# MCU.net
KiCad netlist of a schematic drawn in Altium Designer
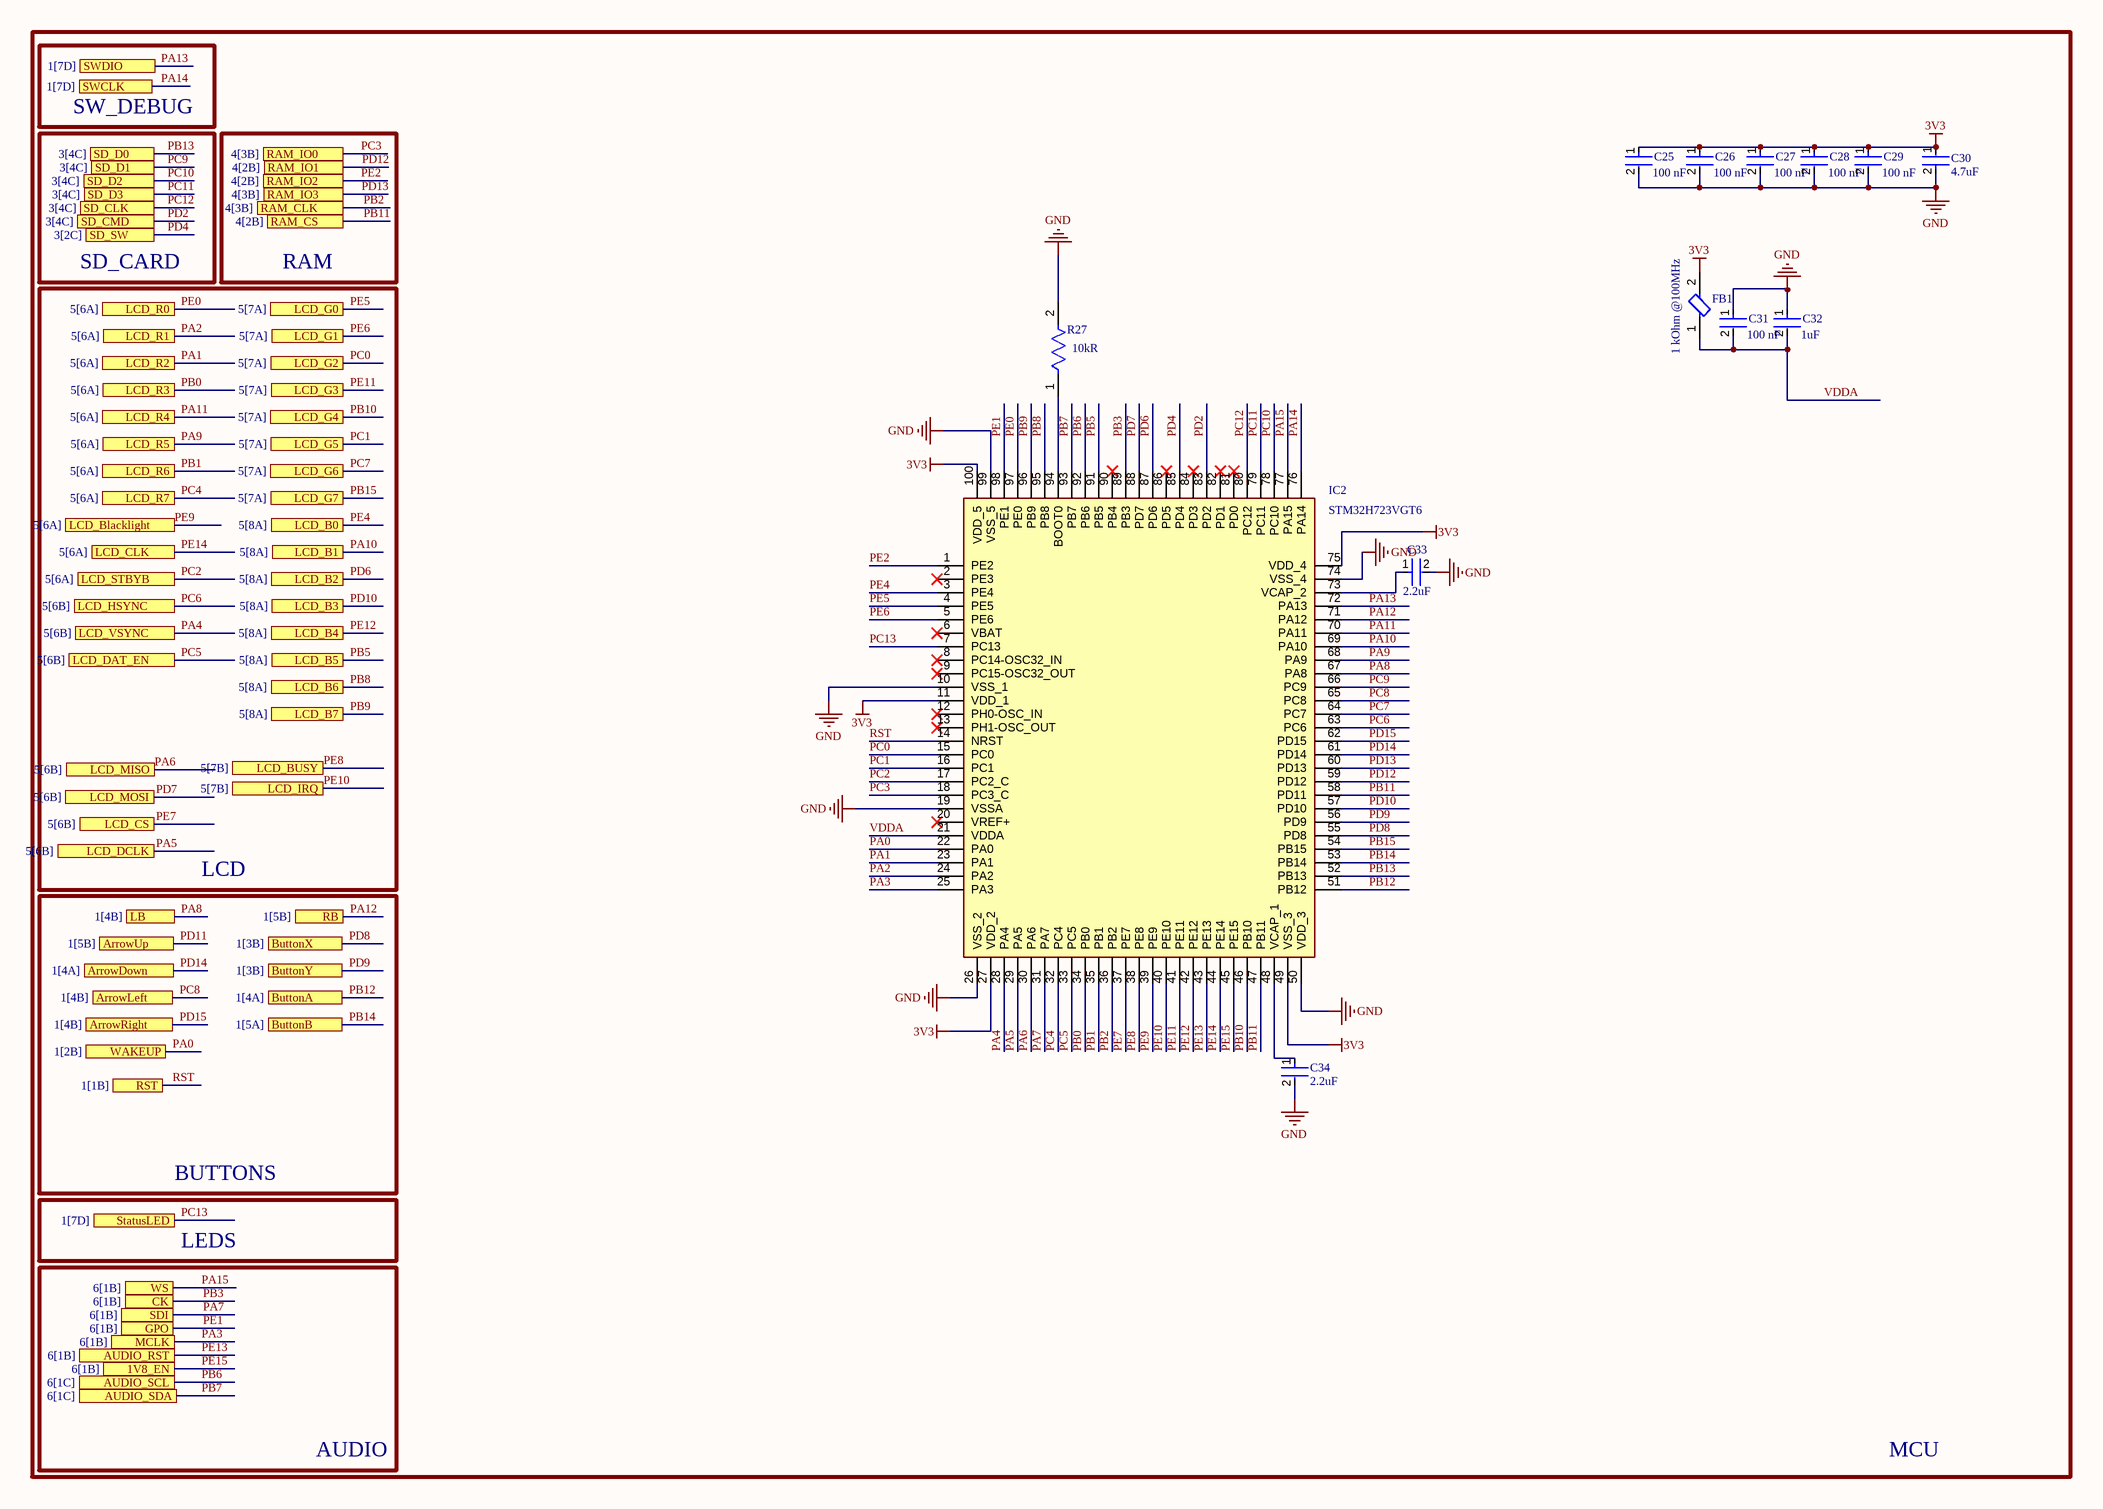
[diagram p0: MCU.SchDoc]

(export (version "E")
  (design (tool "Eeschema 10.0.6"))
  (components
    (comp (ref "C25")
      (value "100 nF")
      (footprint "FP-AC0402-0_5-MFG")
      (description "0.10µF 16V Ceramic Capacitor X7R 0402 (1005 Metric) 0.039\" L x 0.020\" W (1.00mm x 0.50mm)")
      (fields (field (name "MANUFACTURER") "Yageo") (field (name "TOLERANCE") "0.1"))
      (libsource (lib "Altium Content Vault") (part "11868f565c42a9108669ba33697ecf6"))
    )
    (comp (ref "C26")
      (value "100 nF")
      (footprint "FP-AC0402-0_5-MFG")
      (description "0.10µF 16V Ceramic Capacitor X7R 0402 (1005 Metric) 0.039\" L x 0.020\" W (1.00mm x 0.50mm)")
      (fields (field (name "MANUFACTURER") "Yageo") (field (name "TOLERANCE") "0.1"))
      (libsource (lib "Altium Content Vault") (part "11868f565c42a9108669ba33697ecf6"))
    )
    (comp (ref "C27")
      (value "100 nF")
      (footprint "FP-AC0402-0_5-MFG")
      (description "0.10µF 16V Ceramic Capacitor X7R 0402 (1005 Metric) 0.039\" L x 0.020\" W (1.00mm x 0.50mm)")
      (fields (field (name "MANUFACTURER") "Yageo") (field (name "TOLERANCE") "0.1"))
      (libsource (lib "Altium Content Vault") (part "11868f565c42a9108669ba33697ecf6"))
    )
    (comp (ref "C28")
      (value "100 nF")
      (footprint "FP-AC0402-0_5-MFG")
      (description "0.10µF 16V Ceramic Capacitor X7R 0402 (1005 Metric) 0.039\" L x 0.020\" W (1.00mm x 0.50mm)")
      (fields (field (name "MANUFACTURER") "Yageo") (field (name "TOLERANCE") "0.1"))
      (libsource (lib "Altium Content Vault") (part "11868f565c42a9108669ba33697ecf6"))
    )
    (comp (ref "C29")
      (value "100 nF")
      (footprint "FP-AC0402-0_5-MFG")
      (description "0.10µF 16V Ceramic Capacitor X7R 0402 (1005 Metric) 0.039\" L x 0.020\" W (1.00mm x 0.50mm)")
      (fields (field (name "MANUFACTURER") "Yageo") (field (name "TOLERANCE") "0.1"))
      (libsource (lib "Altium Content Vault") (part "11868f565c42a9108669ba33697ecf6"))
    )
    (comp (ref "C30")
      (value "JMK105BBJ475MVHF")
      (footprint "FP-0402-L_1_0_0_15-W_0_5-IPC_B")
      (description "None")
      (fields (field (name "CAPACITANCE") "4.7uF") (field (name "TOLERANCE") "20%"))
      (libsource (lib "Altium Content Vault") (part "236180d848d6139a670b325ea6854c9"))
    )
    (comp (ref "C31")
      (value "100 nF")
      (footprint "FP-AC0402-0_5-MFG")
      (description "0.10µF 16V Ceramic Capacitor X7R 0402 (1005 Metric) 0.039\" L x 0.020\" W (1.00mm x 0.50mm)")
      (fields (field (name "MANUFACTURER") "Yageo") (field (name "TOLERANCE") "0.1"))
      (libsource (lib "Altium Content Vault") (part "11868f565c42a9108669ba33697ecf6"))
    )
    (comp (ref "C32")
      (value "GRM155C70J105KE11D")
      (footprint "FP-GRM155-0_1-IPC_A")
      (description "Chip Multilayer Ceramic Capacitors for General Purpose, 0402, 1.0uF, X7S, 22%, 10%, 6.3V")
      (fields (field (name "CAPACITANCE") "1uF") (field (name "TOLERANCE") "10%"))
      (libsource (lib "Altium Content Vault") (part "11868f565c42a9108669ba33697ecf6"))
    )
    (comp (ref "C33")
      (value "GRM155R61C225KE11D")
      (footprint "FP-GRM155-0_2-IPC_B")
      (description "Chip Multilayer Ceramic Capacitors for General Purpose, 0402, 2.2uF, X5R, 15%, 10%, 16V")
      (fields (field (name "TOLERANCE") "10%") (field (name "CAPACITANCE") "2.2uF"))
      (libsource (lib "Altium Content Vault") (part "b4654b650e69147ec39a6b967a45e02"))
    )
    (comp (ref "C34")
      (value "GRM155R61C225KE11D")
      (footprint "FP-GRM155-0_2-IPC_B")
      (description "Chip Multilayer Ceramic Capacitors for General Purpose, 0402, 2.2uF, X5R, 15%, 10%, 16V")
      (fields (field (name "TOLERANCE") "10%") (field (name "CAPACITANCE") "2.2uF"))
      (libsource (lib "Altium Content Vault") (part "b4654b650e69147ec39a6b967a45e02"))
    )
    (comp (ref "FB1")
      (value "1 kOhm @100MHz")
      (footprint "FP-BLM21-0_2-t0_85-e0_5-d-IPC_A")
      (description "Chip Ferrite Bead, 0805, 1000Ω @ 100MHz, 0.12Ω, 25%, 1.6A")
      (fields (field (name "Comment") "BLM21SP102SN1D"))
      (libsource (lib "Altium Content Vault") (part "5f30dd21d616792df468990f7003faa"))
    )
    (comp (ref "IC2")
      (value "STM32H723VGT6")
      (footprint "SamacSys:QFP50P1600X1600X160-100N")
      (description "Integrated Circuit")
      (fields (field (name "MOUSER PART NUMBER") "511-STM32H723VGT6"))
      (libsource (lib "*") (part "STM32H723VGT6"))
    )
    (comp (ref "R27")
      (value "RK73H1ETTPD1002F")
      (footprint "FP-RK73H1E-IPC_C")
      (description "10kΩ ±1% 0.1W Chip Resistor 0402 Thick Film AEC-Q200 Qualified")
      (fields (field (name "RESISTANCE") "10kR"))
      (libsource (lib "Altium Content Vault") (part "1029c3af85768c4190bb7ad29bc67b5"))
    )
  )
  (nets
    (net (code "3") (name "/PA0") (class "Default")
      (node (ref "IC2") (pin "22") (pinfunction "PA0_22") (pintype "passive"))
    )
    (net (code "4") (name "/PA1") (class "Default")
      (node (ref "IC2") (pin "23") (pinfunction "PA1_23") (pintype "passive"))
    )
    (net (code "5") (name "/PA2") (class "Default")
      (node (ref "IC2") (pin "24") (pinfunction "PA2_24") (pintype "passive"))
    )
    (net (code "6") (name "/PA3") (class "Default")
      (node (ref "IC2") (pin "25") (pinfunction "PA3_25") (pintype "passive"))
    )
    (net (code "7") (name "/PA4") (class "Default")
      (node (ref "IC2") (pin "28") (pinfunction "PA4_28") (pintype "passive"))
    )
    (net (code "8") (name "/PA5") (class "Default")
      (node (ref "IC2") (pin "29") (pinfunction "PA5_29") (pintype "passive"))
    )
    (net (code "9") (name "/PA6") (class "Default")
      (node (ref "IC2") (pin "30") (pinfunction "PA6_30") (pintype "passive"))
    )
    (net (code "10") (name "/PA7") (class "Default")
      (node (ref "IC2") (pin "31") (pinfunction "PA7_31") (pintype "passive"))
    )
    (net (code "11") (name "/PA8") (class "Default")
      (node (ref "IC2") (pin "67") (pinfunction "PA8_67") (pintype "passive"))
    )
    (net (code "12") (name "/PA9") (class "Default")
      (node (ref "IC2") (pin "68") (pinfunction "PA9_68") (pintype "passive"))
    )
    (net (code "13") (name "/PA10") (class "Default")
      (node (ref "IC2") (pin "69") (pinfunction "PA10_69") (pintype "passive"))
    )
    (net (code "14") (name "/PA11") (class "Default")
      (node (ref "IC2") (pin "70") (pinfunction "PA11_70") (pintype "passive"))
    )
    (net (code "15") (name "/PA12") (class "Default")
      (node (ref "IC2") (pin "71") (pinfunction "PA12_71") (pintype "passive"))
    )
    (net (code "16") (name "/PA13") (class "Default")
      (node (ref "IC2") (pin "72") (pinfunction "PA13_72") (pintype "passive"))
    )
    (net (code "17") (name "/PA14") (class "Default")
      (node (ref "IC2") (pin "76") (pinfunction "PA14_76") (pintype "passive"))
    )
    (net (code "18") (name "/PA15") (class "Default")
      (node (ref "IC2") (pin "77") (pinfunction "PA15_77") (pintype "passive"))
    )
    (net (code "19") (name "/PB0") (class "Default")
      (node (ref "IC2") (pin "34") (pinfunction "PB0_34") (pintype "passive"))
    )
    (net (code "20") (name "/PB1") (class "Default")
      (node (ref "IC2") (pin "35") (pinfunction "PB1_35") (pintype "passive"))
    )
    (net (code "21") (name "/PB2") (class "Default")
      (node (ref "IC2") (pin "36") (pinfunction "PB2_36") (pintype "passive"))
    )
    (net (code "22") (name "/PB3") (class "Default")
      (node (ref "IC2") (pin "89") (pinfunction "PB3_89") (pintype "passive"))
    )
    (net (code "23") (name "/PB5") (class "Default")
      (node (ref "IC2") (pin "91") (pinfunction "PB5_91") (pintype "passive"))
    )
    (net (code "24") (name "/PB6") (class "Default")
      (node (ref "IC2") (pin "92") (pinfunction "PB6_92") (pintype "passive"))
    )
    (net (code "25") (name "/PB7") (class "Default")
      (node (ref "IC2") (pin "93") (pinfunction "PB7_93") (pintype "passive"))
    )
    (net (code "26") (name "/PB8") (class "Default")
      (node (ref "IC2") (pin "95") (pinfunction "PB8_95") (pintype "passive"))
    )
    (net (code "27") (name "/PB9") (class "Default")
      (node (ref "IC2") (pin "96") (pinfunction "PB9_96") (pintype "passive"))
    )
    (net (code "28") (name "/PB10") (class "Default")
      (node (ref "IC2") (pin "46") (pinfunction "PB10_46") (pintype "passive"))
    )
    (net (code "29") (name "/PB11") (class "Default")
      (node (ref "IC2") (pin "47") (pinfunction "PB11_47") (pintype "passive"))
      (node (ref "IC2") (pin "58") (pinfunction "PD11_58") (pintype "passive"))
    )
    (net (code "30") (name "/PB12") (class "Default")
      (node (ref "IC2") (pin "51") (pinfunction "PB12_51") (pintype "passive"))
    )
    (net (code "31") (name "/PB13") (class "Default")
      (node (ref "IC2") (pin "52") (pinfunction "PB13_52") (pintype "passive"))
    )
    (net (code "32") (name "/PB14") (class "Default")
      (node (ref "IC2") (pin "53") (pinfunction "PB14_53") (pintype "passive"))
    )
    (net (code "33") (name "/PB15") (class "Default")
      (node (ref "IC2") (pin "54") (pinfunction "PB15_54") (pintype "passive"))
    )
    (net (code "34") (name "/PC0") (class "Default")
      (node (ref "IC2") (pin "15") (pinfunction "PC0_15") (pintype "passive"))
    )
    (net (code "35") (name "/PC1") (class "Default")
      (node (ref "IC2") (pin "16") (pinfunction "PC1_16") (pintype "passive"))
    )
    (net (code "36") (name "/PC2") (class "Default")
      (node (ref "IC2") (pin "17") (pinfunction "PC2_C_17") (pintype "passive"))
    )
    (net (code "37") (name "/PC3") (class "Default")
      (node (ref "IC2") (pin "18") (pinfunction "PC3_C_18") (pintype "passive"))
    )
    (net (code "38") (name "/PC4") (class "Default")
      (node (ref "IC2") (pin "32") (pinfunction "PC4_32") (pintype "passive"))
    )
    (net (code "39") (name "/PC5") (class "Default")
      (node (ref "IC2") (pin "33") (pinfunction "PC5_33") (pintype "passive"))
    )
    (net (code "40") (name "/PC6") (class "Default")
      (node (ref "IC2") (pin "63") (pinfunction "PC6_63") (pintype "passive"))
    )
    (net (code "41") (name "/PC7") (class "Default")
      (node (ref "IC2") (pin "64") (pinfunction "PC7_64") (pintype "passive"))
    )
    (net (code "42") (name "/PC8") (class "Default")
      (node (ref "IC2") (pin "65") (pinfunction "PC8_65") (pintype "passive"))
    )
    (net (code "43") (name "/PC9") (class "Default")
      (node (ref "IC2") (pin "66") (pinfunction "PC9_66") (pintype "passive"))
    )
    (net (code "44") (name "/PC10") (class "Default")
      (node (ref "IC2") (pin "78") (pinfunction "PC10_78") (pintype "passive"))
    )
    (net (code "45") (name "/PC11") (class "Default")
      (node (ref "IC2") (pin "79") (pinfunction "PC11_79") (pintype "passive"))
    )
    (net (code "46") (name "/PC12") (class "Default")
      (node (ref "IC2") (pin "80") (pinfunction "PC12_80") (pintype "passive"))
    )
    (net (code "47") (name "/PC13") (class "Default")
      (node (ref "IC2") (pin "7") (pinfunction "PC13_7") (pintype "passive"))
    )
    (net (code "48") (name "/PD2") (class "Default")
      (node (ref "IC2") (pin "83") (pinfunction "PD2_83") (pintype "passive"))
    )
    (net (code "49") (name "/PD4") (class "Default")
      (node (ref "IC2") (pin "85") (pinfunction "PD4_85") (pintype "passive"))
    )
    (net (code "50") (name "/PD6") (class "Default")
      (node (ref "IC2") (pin "87") (pinfunction "PD6_87") (pintype "passive"))
    )
    (net (code "51") (name "/PD7") (class "Default")
      (node (ref "IC2") (pin "88") (pinfunction "PD7_88") (pintype "passive"))
    )
    (net (code "52") (name "/PD8") (class "Default")
      (node (ref "IC2") (pin "55") (pinfunction "PD8_55") (pintype "passive"))
    )
    (net (code "53") (name "/PD9") (class "Default")
      (node (ref "IC2") (pin "56") (pinfunction "PD9_56") (pintype "passive"))
    )
    (net (code "54") (name "/PD10") (class "Default")
      (node (ref "IC2") (pin "57") (pinfunction "PD10_57") (pintype "passive"))
    )
    (net (code "56") (name "/PD12") (class "Default")
      (node (ref "IC2") (pin "59") (pinfunction "PD12_59") (pintype "passive"))
    )
    (net (code "57") (name "/PD13") (class "Default")
      (node (ref "IC2") (pin "60") (pinfunction "PD13_60") (pintype "passive"))
    )
    (net (code "58") (name "/PD14") (class "Default")
      (node (ref "IC2") (pin "61") (pinfunction "PD14_61") (pintype "passive"))
    )
    (net (code "59") (name "/PD15") (class "Default")
      (node (ref "IC2") (pin "62") (pinfunction "PD15_62") (pintype "passive"))
    )
    (net (code "60") (name "/PE0") (class "Default")
      (node (ref "IC2") (pin "97") (pinfunction "PE0_97") (pintype "passive"))
    )
    (net (code "61") (name "/PE1") (class "Default")
      (node (ref "IC2") (pin "98") (pinfunction "PE1_98") (pintype "passive"))
    )
    (net (code "62") (name "/PE2") (class "Default")
      (node (ref "IC2") (pin "1") (pinfunction "PE2_1") (pintype "passive"))
    )
    (net (code "63") (name "/PE4") (class "Default")
      (node (ref "IC2") (pin "3") (pinfunction "PE4_3") (pintype "passive"))
    )
    (net (code "64") (name "/PE5") (class "Default")
      (node (ref "IC2") (pin "4") (pinfunction "PE5_4") (pintype "passive"))
    )
    (net (code "65") (name "/PE6") (class "Default")
      (node (ref "IC2") (pin "5") (pinfunction "PE6_5") (pintype "passive"))
    )
    (net (code "66") (name "/PE7") (class "Default")
      (node (ref "IC2") (pin "37") (pinfunction "PE7_37") (pintype "passive"))
    )
    (net (code "67") (name "/PE8") (class "Default")
      (node (ref "IC2") (pin "38") (pinfunction "PE8_38") (pintype "passive"))
    )
    (net (code "68") (name "/PE9") (class "Default")
      (node (ref "IC2") (pin "39") (pinfunction "PE9_39") (pintype "passive"))
    )
    (net (code "69") (name "/PE10") (class "Default")
      (node (ref "IC2") (pin "40") (pinfunction "PE10_40") (pintype "passive"))
    )
    (net (code "70") (name "/PE11") (class "Default")
      (node (ref "IC2") (pin "41") (pinfunction "PE11_41") (pintype "passive"))
    )
    (net (code "71") (name "/PE12") (class "Default")
      (node (ref "IC2") (pin "42") (pinfunction "PE12_42") (pintype "passive"))
    )
    (net (code "72") (name "/PE13") (class "Default")
      (node (ref "IC2") (pin "43") (pinfunction "PE13_43") (pintype "passive"))
    )
    (net (code "73") (name "/PE14") (class "Default")
      (node (ref "IC2") (pin "44") (pinfunction "PE14_44") (pintype "passive"))
    )
    (net (code "74") (name "/PE15") (class "Default")
      (node (ref "IC2") (pin "45") (pinfunction "PE15_45") (pintype "passive"))
    )
    (net (code "75") (name "/RST") (class "Default")
      (node (ref "IC2") (pin "14") (pinfunction "NRST_14") (pintype "passive"))
    )
    (net (code "76") (name "/VDDA") (class "Default")
      (node (ref "C31") (pin "2") (pinfunction "2_2") (pintype "passive"))
      (node (ref "C32") (pin "2") (pinfunction "2_2") (pintype "passive"))
      (node (ref "FB1") (pin "1") (pinfunction "1_1") (pintype "passive"))
      (node (ref "IC2") (pin "21") (pinfunction "VDDA_21") (pintype "passive"))
    )
    (net (code "77") (name "3V3") (class "Default")
      (node (ref "C25") (pin "1") (pinfunction "1_1") (pintype "passive"))
      (node (ref "C26") (pin "1") (pinfunction "1_1") (pintype "passive"))
      (node (ref "C27") (pin "1") (pinfunction "1_1") (pintype "passive"))
      (node (ref "C28") (pin "1") (pinfunction "1_1") (pintype "passive"))
      (node (ref "C29") (pin "1") (pinfunction "1_1") (pintype "passive"))
      (node (ref "C30") (pin "1") (pinfunction "1_1") (pintype "passive"))
      (node (ref "FB1") (pin "2") (pinfunction "2_2") (pintype "passive"))
      (node (ref "IC2") (pin "100") (pinfunction "VDD_5_100") (pintype "passive"))
      (node (ref "IC2") (pin "11") (pinfunction "VDD_1_11") (pintype "passive"))
      (node (ref "IC2") (pin "27") (pinfunction "VDD_2_27") (pintype "passive"))
      (node (ref "IC2") (pin "49") (pinfunction "VSS_3_49") (pintype "passive"))
      (node (ref "IC2") (pin "75") (pinfunction "VDD_4_75") (pintype "passive"))
    )
    (net (code "78") (name "GND") (class "Default")
      (node (ref "C25") (pin "2") (pinfunction "2_2") (pintype "passive"))
      (node (ref "C26") (pin "2") (pinfunction "2_2") (pintype "passive"))
      (node (ref "C27") (pin "2") (pinfunction "2_2") (pintype "passive"))
      (node (ref "C28") (pin "2") (pinfunction "2_2") (pintype "passive"))
      (node (ref "C29") (pin "2") (pinfunction "2_2") (pintype "passive"))
      (node (ref "C30") (pin "2") (pinfunction "2_2") (pintype "passive"))
      (node (ref "C31") (pin "1") (pinfunction "1_1") (pintype "passive"))
      (node (ref "C32") (pin "1") (pinfunction "1_1") (pintype "passive"))
      (node (ref "C33") (pin "2") (pinfunction "2_2") (pintype "passive"))
      (node (ref "C34") (pin "2") (pinfunction "2_2") (pintype "passive"))
      (node (ref "IC2") (pin "10") (pinfunction "VSS_1_10") (pintype "passive"))
      (node (ref "IC2") (pin "19") (pinfunction "VSSA_19") (pintype "passive"))
      (node (ref "IC2") (pin "26") (pinfunction "VSS_2_26") (pintype "passive"))
      (node (ref "IC2") (pin "50") (pinfunction "VDD_3_50") (pintype "passive"))
      (node (ref "IC2") (pin "74") (pinfunction "VSS_4_74") (pintype "passive"))
      (node (ref "IC2") (pin "99") (pinfunction "VSS_5_99") (pintype "passive"))
      (node (ref "R27") (pin "2") (pinfunction "2_2") (pintype "passive"))
    )
    (net (code "79") (name "Net-(IC2-BOOT0)") (class "Default")
      (node (ref "IC2") (pin "94") (pinfunction "BOOT0_94") (pintype "passive"))
      (node (ref "R27") (pin "1") (pinfunction "1_1") (pintype "passive"))
    )
    (net (code "80") (name "Net-(IC2-VCAP_1)") (class "Default")
      (node (ref "C34") (pin "1") (pinfunction "1_1") (pintype "passive"))
      (node (ref "IC2") (pin "48") (pinfunction "VCAP_1_48") (pintype "passive"))
    )
    (net (code "81") (name "Net-(IC2-VCAP_2)") (class "Default")
      (node (ref "C33") (pin "1") (pinfunction "1_1") (pintype "passive"))
      (node (ref "IC2") (pin "73") (pinfunction "VCAP_2_73") (pintype "passive"))
    )
    (net (code "82") (name "unconnected-(IC2-PB4-Pad90)") (class "Default")
      (node (ref "IC2") (pin "90") (pinfunction "PB4_90") (pintype "passive+no_connect"))
    )
    (net (code "83") (name "unconnected-(IC2-PC14-OSC32_IN-Pad8)") (class "Default")
      (node (ref "IC2") (pin "8") (pinfunction "PC14-OSC32_IN_8") (pintype "passive+no_connect"))
    )
    (net (code "84") (name "unconnected-(IC2-PC15-OSC32_OUT-Pad9)") (class "Default")
      (node (ref "IC2") (pin "9") (pinfunction "PC15-OSC32_OUT_9") (pintype "passive+no_connect"))
    )
    (net (code "85") (name "unconnected-(IC2-PD0-Pad81)") (class "Default")
      (node (ref "IC2") (pin "81") (pinfunction "PD0_81") (pintype "passive+no_connect"))
    )
    (net (code "86") (name "unconnected-(IC2-PD1-Pad82)") (class "Default")
      (node (ref "IC2") (pin "82") (pinfunction "PD1_82") (pintype "passive+no_connect"))
    )
    (net (code "87") (name "unconnected-(IC2-PD3-Pad84)") (class "Default")
      (node (ref "IC2") (pin "84") (pinfunction "PD3_84") (pintype "passive+no_connect"))
    )
    (net (code "88") (name "unconnected-(IC2-PD5-Pad86)") (class "Default")
      (node (ref "IC2") (pin "86") (pinfunction "PD5_86") (pintype "passive+no_connect"))
    )
    (net (code "89") (name "unconnected-(IC2-PE3-Pad2)") (class "Default")
      (node (ref "IC2") (pin "2") (pinfunction "PE3_2") (pintype "passive+no_connect"))
    )
    (net (code "90") (name "unconnected-(IC2-PH0-OSC_IN-Pad12)") (class "Default")
      (node (ref "IC2") (pin "12") (pinfunction "PH0-OSC_IN_12") (pintype "passive+no_connect"))
    )
    (net (code "91") (name "unconnected-(IC2-PH1-OSC_OUT-Pad13)") (class "Default")
      (node (ref "IC2") (pin "13") (pinfunction "PH1-OSC_OUT_13") (pintype "passive+no_connect"))
    )
    (net (code "92") (name "unconnected-(IC2-VBAT-Pad6)") (class "Default")
      (node (ref "IC2") (pin "6") (pinfunction "VBAT_6") (pintype "passive+no_connect"))
    )
    (net (code "93") (name "unconnected-(IC2-VREF+-Pad20)") (class "Default")
      (node (ref "IC2") (pin "20") (pinfunction "VREF+_20") (pintype "passive+no_connect"))
    )
  )
)
